# ZHSD-HDMI.net
KiCad netlist of a schematic drawn in Altium Designer
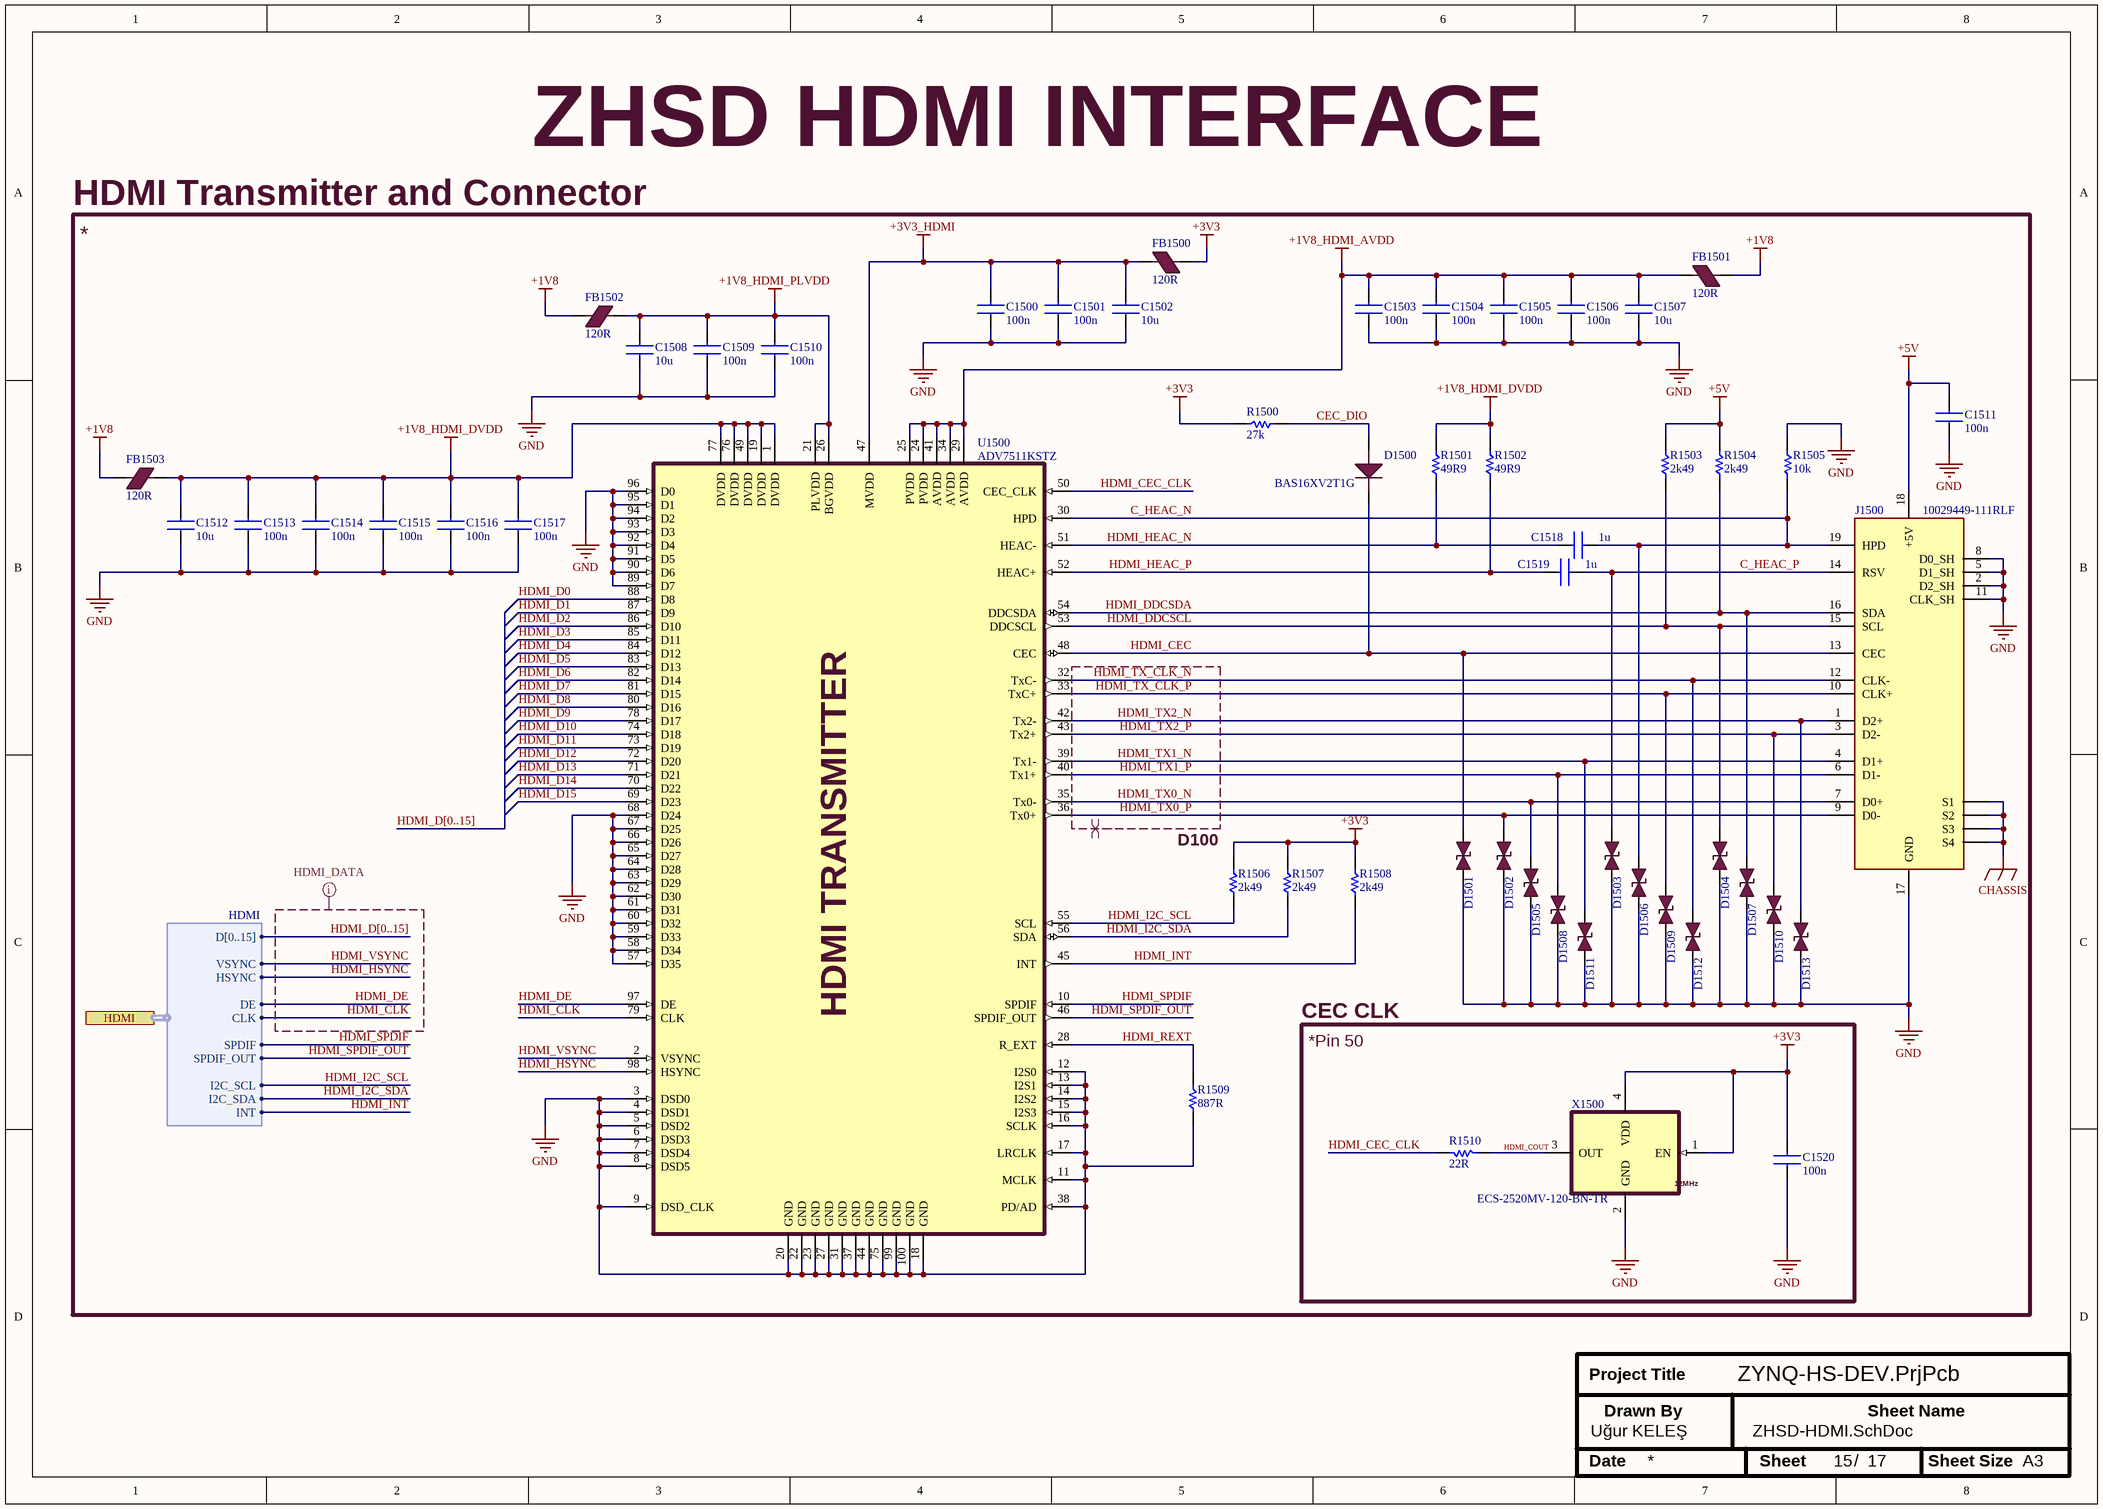
[diagram p0: ZHSD-HDMI.SchDoc]

(export (version "E")
  (design (tool "Eeschema 10.0.6"))
  (components
    (comp (ref "C1500")
      (value "100n")
      (footprint "0603CAPC1608X09N")
      (description "CAP CER 0.1UF 16V X7R 0402 (1005) ±10%")
      (fields (field (name "MANUFACTURER") "Murata Electronics") (field (name "MPN") "GRM155R71C104KA88J"))
      (libsource (lib "UK_Library") (part "GRM155R71C104KA88J"))
    )
    (comp (ref "C1501")
      (value "100n")
      (footprint "0603CAPC1608X09N")
      (description "CAP CER 0.1UF 16V X7R 0402 (1005) ±10%")
      (fields (field (name "MANUFACTURER") "Murata Electronics") (field (name "MPN") "GRM155R71C104KA88J"))
      (libsource (lib "UK_Library") (part "GRM155R71C104KA88J"))
    )
    (comp (ref "C1502")
      (value "10u")
      (footprint "0603CAPC1608X09N")
      (description "CAP CER 10UF 10V X7R 0603 (1608) ±20%")
      (fields (field (name "MANUFACTURER") "Murata Electronics") (field (name "MPN") "GRM188Z71A106MA73D"))
      (libsource (lib "UK_Library") (part "GRM188Z71A106MA73D"))
    )
    (comp (ref "C1503")
      (value "100n")
      (footprint "0603CAPC1608X09N")
      (description "CAP CER 0.1UF 16V X7R 0402 (1005) ±10%")
      (fields (field (name "MANUFACTURER") "Murata Electronics") (field (name "MPN") "GRM155R71C104KA88J"))
      (libsource (lib "UK_Library") (part "GRM155R71C104KA88J"))
    )
    (comp (ref "C1504")
      (value "100n")
      (footprint "0603CAPC1608X09N")
      (description "CAP CER 0.1UF 16V X7R 0402 (1005) ±10%")
      (fields (field (name "MANUFACTURER") "Murata Electronics") (field (name "MPN") "GRM155R71C104KA88J"))
      (libsource (lib "UK_Library") (part "GRM155R71C104KA88J"))
    )
    (comp (ref "C1505")
      (value "100n")
      (footprint "0603CAPC1608X09N")
      (description "CAP CER 0.1UF 16V X7R 0402 (1005) ±10%")
      (fields (field (name "MANUFACTURER") "Murata Electronics") (field (name "MPN") "GRM155R71C104KA88J"))
      (libsource (lib "UK_Library") (part "GRM155R71C104KA88J"))
    )
    (comp (ref "C1506")
      (value "100n")
      (footprint "0603CAPC1608X09N")
      (description "CAP CER 0.1UF 16V X7R 0402 (1005) ±10%")
      (fields (field (name "MANUFACTURER") "Murata Electronics") (field (name "MPN") "GRM155R71C104KA88J"))
      (libsource (lib "UK_Library") (part "GRM155R71C104KA88J"))
    )
    (comp (ref "C1507")
      (value "10u")
      (footprint "0603CAPC1608X09N")
      (description "CAP CER 10UF 10V X7R 0603 (1608) ±20%")
      (fields (field (name "MANUFACTURER") "Murata Electronics") (field (name "MPN") "GRM188Z71A106MA73D"))
      (libsource (lib "UK_Library") (part "GRM188Z71A106MA73D"))
    )
    (comp (ref "C1508")
      (value "10u")
      (footprint "0603CAPC1608X09N")
      (description "CAP CER 10UF 10V X7R 0603 (1608) ±20%")
      (fields (field (name "MANUFACTURER") "Murata Electronics") (field (name "MPN") "GRM188Z71A106MA73D"))
      (libsource (lib "UK_Library") (part "GRM188Z71A106MA73D"))
    )
    (comp (ref "C1509")
      (value "100n")
      (footprint "0603CAPC1608X09N")
      (description "CAP CER 0.1UF 16V X7R 0402 (1005) ±10%")
      (fields (field (name "MANUFACTURER") "Murata Electronics") (field (name "MPN") "GRM155R71C104KA88J"))
      (libsource (lib "UK_Library") (part "GRM155R71C104KA88J"))
    )
    (comp (ref "C1510")
      (value "100n")
      (footprint "0603CAPC1608X09N")
      (description "CAP CER 0.1UF 16V X7R 0402 (1005) ±10%")
      (fields (field (name "MANUFACTURER") "Murata Electronics") (field (name "MPN") "GRM155R71C104KA88J"))
      (libsource (lib "UK_Library") (part "GRM155R71C104KA88J"))
    )
    (comp (ref "C1511")
      (value "100n")
      (footprint "0603CAPC1608X09N")
      (description "CAP CER 0.1UF 16V X7R 0402 (1005) ±10%")
      (fields (field (name "MANUFACTURER") "Murata Electronics") (field (name "MPN") "GRM155R71C104KA88J"))
      (libsource (lib "UK_Library") (part "GRM155R71C104KA88J"))
    )
    (comp (ref "C1512")
      (value "10u")
      (footprint "0603CAPC1608X09N")
      (description "CAP CER 10UF 10V X7R 0603 (1608) ±20%")
      (fields (field (name "MANUFACTURER") "Murata Electronics") (field (name "MPN") "GRM188Z71A106MA73D"))
      (libsource (lib "UK_Library") (part "GRM188Z71A106MA73D"))
    )
    (comp (ref "C1513")
      (value "100n")
      (footprint "0603CAPC1608X09N")
      (description "CAP CER 0.1UF 16V X7R 0402 (1005) ±10%")
      (fields (field (name "MANUFACTURER") "Murata Electronics") (field (name "MPN") "GRM155R71C104KA88J"))
      (libsource (lib "UK_Library") (part "GRM155R71C104KA88J"))
    )
    (comp (ref "C1514")
      (value "100n")
      (footprint "0603CAPC1608X09N")
      (description "CAP CER 0.1UF 16V X7R 0402 (1005) ±10%")
      (fields (field (name "MANUFACTURER") "Murata Electronics") (field (name "MPN") "GRM155R71C104KA88J"))
      (libsource (lib "UK_Library") (part "GRM155R71C104KA88J"))
    )
    (comp (ref "C1515")
      (value "100n")
      (footprint "0603CAPC1608X09N")
      (description "CAP CER 0.1UF 16V X7R 0402 (1005) ±10%")
      (fields (field (name "MANUFACTURER") "Murata Electronics") (field (name "MPN") "GRM155R71C104KA88J"))
      (libsource (lib "UK_Library") (part "GRM155R71C104KA88J"))
    )
    (comp (ref "C1516")
      (value "100n")
      (footprint "0603CAPC1608X09N")
      (description "CAP CER 0.1UF 16V X7R 0402 (1005) ±10%")
      (fields (field (name "MANUFACTURER") "Murata Electronics") (field (name "MPN") "GRM155R71C104KA88J"))
      (libsource (lib "UK_Library") (part "GRM155R71C104KA88J"))
    )
    (comp (ref "C1517")
      (value "100n")
      (footprint "0603CAPC1608X09N")
      (description "CAP CER 0.1UF 16V X7R 0402 (1005) ±10%")
      (fields (field (name "MANUFACTURER") "Murata Electronics") (field (name "MPN") "GRM155R71C104KA88J"))
      (libsource (lib "UK_Library") (part "GRM155R71C104KA88J"))
    )
    (comp (ref "C1518")
      (value "1u")
      (footprint "0603CAPC1608X09N")
      (description "CAP CER 1UF 25V X5R 0603 (1608) ±10%")
      (fields
        (field (name "MANUFACTURER") "Murata Power Solutions Inc.")
        (field (name "MPN") "GRM188R61E105KA12D")
      )
      (libsource (lib "UK_Library") (part "GRM188R61E105KA12D"))
    )
    (comp (ref "C1519")
      (value "1u")
      (footprint "0603CAPC1608X09N")
      (description "CAP CER 1UF 25V X5R 0603 (1608) ±10%")
      (fields
        (field (name "MANUFACTURER") "Murata Power Solutions Inc.")
        (field (name "MPN") "GRM188R61E105KA12D")
      )
      (libsource (lib "UK_Library") (part "GRM188R61E105KA12D"))
    )
    (comp (ref "C1520")
      (value "100n")
      (footprint "0603CAPC1608X09N")
      (description "CAP CER 0.1UF 50V X7R 0603 (1608) ±10%")
      (fields (field (name "MANUFACTURER") "KEMET") (field (name "MPN") "C0603C104K5RACTU"))
      (libsource (lib "UK_Library") (part "C0603C104K5RACTU"))
    )
    (comp (ref "D1500")
      (value "BAS16XV2T1G")
      (footprint "SODFL160X50-2N")
      (description "DIODE STANDARD 100V 200MA SOD523")
      (fields (field (name "MANUFACTURER") "onsemi"))
      (libsource (lib "UK_Library") (part "BAS16XV2T1G"))
    )
    (comp (ref "D1501")
      (value "B72590D0050H160")
      (footprint "0402DIOC1005X06N")
      (description "Varistor 1 Circuit Surface Mount, MLCV 0402 (1005 Metric)")
      (fields (field (name "MANUFACTURER") "EPCOS - TDK Electronics"))
      (libsource (lib "UK_Library") (part "B72590D0050H160"))
    )
    (comp (ref "D1502")
      (value "B72590D0050H160")
      (footprint "0402DIOC1005X06N")
      (description "Varistor 1 Circuit Surface Mount, MLCV 0402 (1005 Metric)")
      (fields (field (name "MANUFACTURER") "EPCOS - TDK Electronics"))
      (libsource (lib "UK_Library") (part "B72590D0050H160"))
    )
    (comp (ref "D1503")
      (value "B72590D0050H160")
      (footprint "0402DIOC1005X06N")
      (description "Varistor 1 Circuit Surface Mount, MLCV 0402 (1005 Metric)")
      (fields (field (name "MANUFACTURER") "EPCOS - TDK Electronics"))
      (libsource (lib "UK_Library") (part "B72590D0050H160"))
    )
    (comp (ref "D1504")
      (value "B72590D0050H160")
      (footprint "0402DIOC1005X06N")
      (description "Varistor 1 Circuit Surface Mount, MLCV 0402 (1005 Metric)")
      (fields (field (name "MANUFACTURER") "EPCOS - TDK Electronics"))
      (libsource (lib "UK_Library") (part "B72590D0050H160"))
    )
    (comp (ref "D1505")
      (value "B72590D0050H160")
      (footprint "0402DIOC1005X06N")
      (description "Varistor 1 Circuit Surface Mount, MLCV 0402 (1005 Metric)")
      (fields (field (name "MANUFACTURER") "EPCOS - TDK Electronics"))
      (libsource (lib "UK_Library") (part "B72590D0050H160"))
    )
    (comp (ref "D1506")
      (value "B72590D0050H160")
      (footprint "0402DIOC1005X06N")
      (description "Varistor 1 Circuit Surface Mount, MLCV 0402 (1005 Metric)")
      (fields (field (name "MANUFACTURER") "EPCOS - TDK Electronics"))
      (libsource (lib "UK_Library") (part "B72590D0050H160"))
    )
    (comp (ref "D1507")
      (value "B72590D0050H160")
      (footprint "0402DIOC1005X06N")
      (description "Varistor 1 Circuit Surface Mount, MLCV 0402 (1005 Metric)")
      (fields (field (name "MANUFACTURER") "EPCOS - TDK Electronics"))
      (libsource (lib "UK_Library") (part "B72590D0050H160"))
    )
    (comp (ref "D1508")
      (value "B72590D0050H160")
      (footprint "0402DIOC1005X06N")
      (description "Varistor 1 Circuit Surface Mount, MLCV 0402 (1005 Metric)")
      (fields (field (name "MANUFACTURER") "EPCOS - TDK Electronics"))
      (libsource (lib "UK_Library") (part "B72590D0050H160"))
    )
    (comp (ref "D1509")
      (value "B72590D0050H160")
      (footprint "0402DIOC1005X06N")
      (description "Varistor 1 Circuit Surface Mount, MLCV 0402 (1005 Metric)")
      (fields (field (name "MANUFACTURER") "EPCOS - TDK Electronics"))
      (libsource (lib "UK_Library") (part "B72590D0050H160"))
    )
    (comp (ref "D1510")
      (value "B72590D0050H160")
      (footprint "0402DIOC1005X06N")
      (description "Varistor 1 Circuit Surface Mount, MLCV 0402 (1005 Metric)")
      (fields (field (name "MANUFACTURER") "EPCOS - TDK Electronics"))
      (libsource (lib "UK_Library") (part "B72590D0050H160"))
    )
    (comp (ref "D1511")
      (value "B72590D0050H160")
      (footprint "0402DIOC1005X06N")
      (description "Varistor 1 Circuit Surface Mount, MLCV 0402 (1005 Metric)")
      (fields (field (name "MANUFACTURER") "EPCOS - TDK Electronics"))
      (libsource (lib "UK_Library") (part "B72590D0050H160"))
    )
    (comp (ref "D1512")
      (value "B72590D0050H160")
      (footprint "0402DIOC1005X06N")
      (description "Varistor 1 Circuit Surface Mount, MLCV 0402 (1005 Metric)")
      (fields (field (name "MANUFACTURER") "EPCOS - TDK Electronics"))
      (libsource (lib "UK_Library") (part "B72590D0050H160"))
    )
    (comp (ref "D1513")
      (value "B72590D0050H160")
      (footprint "0402DIOC1005X06N")
      (description "Varistor 1 Circuit Surface Mount, MLCV 0402 (1005 Metric)")
      (fields (field (name "MANUFACTURER") "EPCOS - TDK Electronics"))
      (libsource (lib "UK_Library") (part "B72590D0050H160"))
    )
    (comp (ref "FB1500")
      (value "120R")
      (footprint "0603INDC1608X08N")
      (description "FERRITE BEAD 120 OHM 0603 (1608) 3A 25mOhm")
      (fields (field (name "MANUFACTURER") "Murata Electronics") (field (name "MPN") "BLM18SG121TN1D"))
      (libsource (lib "UK_Library") (part "BLM18SG121TN1D"))
    )
    (comp (ref "FB1501")
      (value "120R")
      (footprint "0603INDC1608X08N")
      (description "FERRITE BEAD 120 OHM 0603 (1608) 3A 25mOhm")
      (fields (field (name "MANUFACTURER") "Murata Electronics") (field (name "MPN") "BLM18SG121TN1D"))
      (libsource (lib "UK_Library") (part "BLM18SG121TN1D"))
    )
    (comp (ref "FB1502")
      (value "120R")
      (footprint "0603INDC1608X08N")
      (description "FERRITE BEAD 120 OHM 0603 (1608) 3A 25mOhm")
      (fields (field (name "MANUFACTURER") "Murata Electronics") (field (name "MPN") "BLM18SG121TN1D"))
      (libsource (lib "UK_Library") (part "BLM18SG121TN1D"))
    )
    (comp (ref "FB1503")
      (value "120R")
      (footprint "0603INDC1608X08N")
      (description "FERRITE BEAD 120 OHM 0603 (1608) 3A 25mOhm")
      (fields (field (name "MANUFACTURER") "Murata Electronics") (field (name "MPN") "BLM18SG121TN1D"))
      (libsource (lib "UK_Library") (part "BLM18SG121TN1D"))
    )
    (comp (ref "J1500")
      (value "10029449-111RLF")
      (footprint "AMPHENOL_10029449-111RLF")
      (description "CONN RCPT 1.4 HDMI 19POS SMD R/A")
      (fields (field (name "MANUFACTURER") "Amphenol ICC (FCI)"))
      (libsource (lib "UK_Library") (part "10029449-111RLF"))
    )
    (comp (ref "R1500")
      (value "27k")
      (footprint "0402RESC1005X04N")
      (description "RES 27K OHM 1% 1/16W 0402 (1005)")
      (fields (field (name "MANUFACTURER") "YAGEO") (field (name "MPN") "RC0402FR-0727KL"))
      (libsource (lib "UK_Library") (part "RC0402FR-0727KL"))
    )
    (comp (ref "R1501")
      (value "49R9")
      (footprint "0402RESC1005X04N")
      (description "RES 49.9 OHM 1% 1/16W 0402 (1005)")
      (fields (field (name "MANUFACTURER") "YAGEO") (field (name "MPN") "RC0402FR-0749R9L"))
      (libsource (lib "UK_Library") (part "RC0402FR-0749R9L"))
    )
    (comp (ref "R1502")
      (value "49R9")
      (footprint "0402RESC1005X04N")
      (description "RES 49.9 OHM 1% 1/16W 0402 (1005)")
      (fields (field (name "MANUFACTURER") "YAGEO") (field (name "MPN") "RC0402FR-0749R9L"))
      (libsource (lib "UK_Library") (part "RC0402FR-0749R9L"))
    )
    (comp (ref "R1503")
      (value "2k49")
      (footprint "0402RESC1005X04N")
      (description "RES 2.49K OHM 1% 1/16W 0402 (1005)")
      (fields (field (name "MANUFACTURER") "YAGEO") (field (name "MPN") "RC0402FR-132K49L"))
      (libsource (lib "UK_Library") (part "RC0402FR-132K49L"))
    )
    (comp (ref "R1504")
      (value "2k49")
      (footprint "0402RESC1005X04N")
      (description "RES 2.49K OHM 1% 1/16W 0402 (1005)")
      (fields (field (name "MANUFACTURER") "YAGEO") (field (name "MPN") "RC0402FR-132K49L"))
      (libsource (lib "UK_Library") (part "RC0402FR-132K49L"))
    )
    (comp (ref "R1505")
      (value "10k")
      (footprint "0603RESC1608X05N")
      (description "RES 10K OHM 1% 1/10W 0603(1608)")
      (fields (field (name "MANUFACTURER") "YAGEO") (field (name "MPN") "RC0603FR-0710KL"))
      (libsource (lib "UK_Library") (part "RC0603FR-0710KL"))
    )
    (comp (ref "R1506")
      (value "2k49")
      (footprint "0402RESC1005X04N")
      (description "RES 2.49K OHM 1% 1/16W 0402 (1005)")
      (fields (field (name "MANUFACTURER") "YAGEO") (field (name "MPN") "RC0402FR-132K49L"))
      (libsource (lib "UK_Library") (part "RC0402FR-132K49L"))
    )
    (comp (ref "R1507")
      (value "2k49")
      (footprint "0402RESC1005X04N")
      (description "RES 2.49K OHM 1% 1/16W 0402 (1005)")
      (fields (field (name "MANUFACTURER") "YAGEO") (field (name "MPN") "RC0402FR-132K49L"))
      (libsource (lib "UK_Library") (part "RC0402FR-132K49L"))
    )
    (comp (ref "R1508")
      (value "2k49")
      (footprint "0402RESC1005X04N")
      (description "RES 2.49K OHM 1% 1/16W 0402 (1005)")
      (fields (field (name "MANUFACTURER") "YAGEO") (field (name "MPN") "RC0402FR-132K49L"))
      (libsource (lib "UK_Library") (part "RC0402FR-132K49L"))
    )
    (comp (ref "R1509")
      (value "887R")
      (footprint "0603RESC1608X05N")
      (description "RES 887 OHM 1% 1/10W 0603 (1608)")
      (fields (field (name "MANUFACTURER") "YAGEO") (field (name "MPN") "RC0603FR-07887RL"))
      (libsource (lib "UK_Library") (part "RC0603FR-07887RL"))
    )
    (comp (ref "R1510")
      (value "22R")
      (footprint "0603RESC1608X05N")
      (description "RES 22 OHM 1% 1/10W 0603 (1608)")
      (fields (field (name "MANUFACTURER") "YAGEO") (field (name "MPN") "RC0603FR-0722RL"))
      (libsource (lib "UK_Library") (part "RC0603FR-0722RL"))
    )
    (comp (ref "U1500")
      (value "ADV7511KSTZ")
      (footprint "LQFP50P1600X1600X160-100N")
      (description "225 MHz, High Performance HDMI® Transmitter with ARC")
      (fields (field (name "MANUFACTURER") "Analog Devices Inc./Maxim Integrated"))
      (libsource (lib "UK_Library") (part "ADV7511KSTZ"))
    )
    (comp (ref "X1500")
      (value "ECS-2520MV-120-BN-TR")
      (footprint "XTAL_2520")
      (description "XTAL OSC XO 12.0000MHZ CMOS SMD")
      (fields (field (name "MANUFACTURER") "ECS Inc."))
      (libsource (lib "UK_Library") (part "ECS-2520MV-120-BN-TR"))
    )
  )
  (nets
    (net (code "2") (name "+1V8") (class "Default")
      (node (ref "FB1501") (pin "1") (pinfunction "1_1") (pintype "passive"))
      (node (ref "FB1502") (pin "1") (pinfunction "1_1") (pintype "passive"))
      (node (ref "FB1503") (pin "1") (pinfunction "1_1") (pintype "passive"))
    )
    (net (code "3") (name "+1V8_HDMI_AVDD") (class "Default")
      (node (ref "C1503") (pin "2") (pinfunction "2_2") (pintype "passive"))
      (node (ref "C1504") (pin "2") (pinfunction "2_2") (pintype "passive"))
      (node (ref "C1505") (pin "2") (pinfunction "2_2") (pintype "passive"))
      (node (ref "C1506") (pin "2") (pinfunction "2_2") (pintype "passive"))
      (node (ref "C1507") (pin "2") (pinfunction "2_2") (pintype "passive"))
      (node (ref "FB1501") (pin "2") (pinfunction "2_2") (pintype "passive"))
      (node (ref "U1500") (pin "24") (pinfunction "PVDD_24") (pintype "power_in"))
      (node (ref "U1500") (pin "25") (pinfunction "PVDD_25") (pintype "power_in"))
      (node (ref "U1500") (pin "29") (pinfunction "AVDD_29") (pintype "power_in"))
      (node (ref "U1500") (pin "34") (pinfunction "AVDD_34") (pintype "power_in"))
      (node (ref "U1500") (pin "41") (pinfunction "AVDD_41") (pintype "power_in"))
    )
    (net (code "4") (name "+1V8_HDMI_DVDD") (class "Default")
      (node (ref "C1512") (pin "2") (pinfunction "2_2") (pintype "passive"))
      (node (ref "C1513") (pin "2") (pinfunction "2_2") (pintype "passive"))
      (node (ref "C1514") (pin "2") (pinfunction "2_2") (pintype "passive"))
      (node (ref "C1515") (pin "2") (pinfunction "2_2") (pintype "passive"))
      (node (ref "C1516") (pin "2") (pinfunction "2_2") (pintype "passive"))
      (node (ref "C1517") (pin "2") (pinfunction "2_2") (pintype "passive"))
      (node (ref "FB1503") (pin "2") (pinfunction "2_2") (pintype "passive"))
      (node (ref "R1501") (pin "2") (pinfunction "2_2") (pintype "passive"))
      (node (ref "R1502") (pin "2") (pinfunction "2_2") (pintype "passive"))
      (node (ref "U1500") (pin "1") (pinfunction "DVDD_1") (pintype "power_in"))
      (node (ref "U1500") (pin "19") (pinfunction "DVDD_19") (pintype "power_in"))
      (node (ref "U1500") (pin "49") (pinfunction "DVDD_49") (pintype "power_in"))
      (node (ref "U1500") (pin "76") (pinfunction "DVDD_76") (pintype "power_in"))
      (node (ref "U1500") (pin "77") (pinfunction "DVDD_77") (pintype "power_in"))
    )
    (net (code "5") (name "+1V8_HDMI_PLVDD") (class "Default")
      (node (ref "C1508") (pin "2") (pinfunction "2_2") (pintype "passive"))
      (node (ref "C1509") (pin "2") (pinfunction "2_2") (pintype "passive"))
      (node (ref "C1510") (pin "2") (pinfunction "2_2") (pintype "passive"))
      (node (ref "FB1502") (pin "2") (pinfunction "2_2") (pintype "passive"))
      (node (ref "U1500") (pin "21") (pinfunction "PLVDD_21") (pintype "power_in"))
      (node (ref "U1500") (pin "26") (pinfunction "BGVDD_26") (pintype "power_in"))
    )
    (net (code "6") (name "+3V3") (class "Default")
      (node (ref "C1520") (pin "2") (pinfunction "2_2") (pintype "passive"))
      (node (ref "FB1500") (pin "1") (pinfunction "1_1") (pintype "passive"))
      (node (ref "R1500") (pin "2") (pinfunction "2_2") (pintype "passive"))
      (node (ref "R1506") (pin "2") (pinfunction "2_2") (pintype "passive"))
      (node (ref "R1507") (pin "2") (pinfunction "2_2") (pintype "passive"))
      (node (ref "R1508") (pin "2") (pinfunction "2_2") (pintype "passive"))
      (node (ref "X1500") (pin "1") (pinfunction "EN_1") (pintype "input"))
      (node (ref "X1500") (pin "4") (pinfunction "VDD_4") (pintype "power_in"))
    )
    (net (code "7") (name "+3V3_HDMI") (class "Default")
      (node (ref "C1500") (pin "2") (pinfunction "2_2") (pintype "passive"))
      (node (ref "C1501") (pin "2") (pinfunction "2_2") (pintype "passive"))
      (node (ref "C1502") (pin "2") (pinfunction "2_2") (pintype "passive"))
      (node (ref "FB1500") (pin "2") (pinfunction "2_2") (pintype "passive"))
      (node (ref "U1500") (pin "47") (pinfunction "MVDD_47") (pintype "power_in"))
    )
    (net (code "8") (name "+5V") (class "Default")
      (node (ref "C1511") (pin "2") (pinfunction "2_2") (pintype "passive"))
      (node (ref "J1500") (pin "18") (pinfunction "+5V_18") (pintype "passive"))
      (node (ref "R1503") (pin "2") (pinfunction "2_2") (pintype "passive"))
      (node (ref "R1504") (pin "2") (pinfunction "2_2") (pintype "passive"))
    )
    (net (code "9") (name "/CEC_DIO") (class "Default")
      (node (ref "D1500") (pin "A") (pinfunction "2_A") (pintype "passive"))
      (node (ref "R1500") (pin "1") (pinfunction "1_1") (pintype "passive"))
    )
    (net (code "10") (name "/C_HEAC_N") (class "Default")
      (node (ref "C1518") (pin "2") (pinfunction "2_2") (pintype "passive"))
      (node (ref "D1506") (pin "2") (pinfunction "2_2") (pintype "passive"))
      (node (ref "J1500") (pin "19") (pinfunction "HPD_19") (pintype "passive"))
      (node (ref "R1505") (pin "2") (pinfunction "2_2") (pintype "passive"))
      (node (ref "U1500") (pin "30") (pinfunction "HPD_30") (pintype "input"))
    )
    (net (code "11") (name "/C_HEAC_P") (class "Default")
      (node (ref "C1519") (pin "2") (pinfunction "2_2") (pintype "passive"))
      (node (ref "D1503") (pin "2") (pinfunction "2_2") (pintype "passive"))
      (node (ref "J1500") (pin "14") (pinfunction "RSV_14") (pintype "passive"))
    )
    (net (code "12") (name "/HDMI_CEC") (class "Default")
      (node (ref "D1500") (pin "C") (pinfunction "1_C") (pintype "passive"))
      (node (ref "D1501") (pin "2") (pinfunction "2_2") (pintype "passive"))
      (node (ref "J1500") (pin "13") (pinfunction "CEC_13") (pintype "passive"))
      (node (ref "U1500") (pin "48") (pinfunction "CEC_48") (pintype "bidirectional"))
    )
    (net (code "13") (name "/HDMI_CEC_CLK") (class "Default")
      (node (ref "R1510") (pin "1") (pinfunction "1_1") (pintype "passive"))
      (node (ref "U1500") (pin "50") (pinfunction "CEC_CLK_50") (pintype "input"))
    )
    (net (code "14") (name "/HDMI_CLK") (class "Default")
      (node (ref "U1500") (pin "79") (pinfunction "CLK_79") (pintype "input"))
    )
    (net (code "15") (name "/HDMI_COUT") (class "Default")
      (node (ref "R1510") (pin "2") (pinfunction "2_2") (pintype "passive"))
      (node (ref "X1500") (pin "3") (pinfunction "OUT_3") (pintype "passive"))
    )
    (net (code "16") (name "/HDMI_D0") (class "Default")
      (node (ref "U1500") (pin "88") (pinfunction "D8_88") (pintype "input"))
    )
    (net (code "17") (name "/HDMI_D1") (class "Default")
      (node (ref "U1500") (pin "87") (pinfunction "D9_87") (pintype "input"))
    )
    (net (code "18") (name "/HDMI_D2") (class "Default")
      (node (ref "U1500") (pin "86") (pinfunction "D10_86") (pintype "input"))
    )
    (net (code "19") (name "/HDMI_D3") (class "Default")
      (node (ref "U1500") (pin "85") (pinfunction "D11_85") (pintype "input"))
    )
    (net (code "20") (name "/HDMI_D4") (class "Default")
      (node (ref "U1500") (pin "84") (pinfunction "D12_84") (pintype "input"))
    )
    (net (code "21") (name "/HDMI_D5") (class "Default")
      (node (ref "U1500") (pin "83") (pinfunction "D13_83") (pintype "input"))
    )
    (net (code "22") (name "/HDMI_D6") (class "Default")
      (node (ref "U1500") (pin "82") (pinfunction "D14_82") (pintype "input"))
    )
    (net (code "23") (name "/HDMI_D7") (class "Default")
      (node (ref "U1500") (pin "81") (pinfunction "D15_81") (pintype "input"))
    )
    (net (code "24") (name "/HDMI_D8") (class "Default")
      (node (ref "U1500") (pin "80") (pinfunction "D16_80") (pintype "input"))
    )
    (net (code "25") (name "/HDMI_D9") (class "Default")
      (node (ref "U1500") (pin "78") (pinfunction "D17_78") (pintype "input"))
    )
    (net (code "26") (name "/HDMI_D10") (class "Default")
      (node (ref "U1500") (pin "74") (pinfunction "D18_74") (pintype "input"))
    )
    (net (code "27") (name "/HDMI_D11") (class "Default")
      (node (ref "U1500") (pin "73") (pinfunction "D19_73") (pintype "input"))
    )
    (net (code "28") (name "/HDMI_D12") (class "Default")
      (node (ref "U1500") (pin "72") (pinfunction "D20_72") (pintype "input"))
    )
    (net (code "29") (name "/HDMI_D13") (class "Default")
      (node (ref "U1500") (pin "71") (pinfunction "D21_71") (pintype "input"))
    )
    (net (code "30") (name "/HDMI_D14") (class "Default")
      (node (ref "U1500") (pin "70") (pinfunction "D22_70") (pintype "input"))
    )
    (net (code "31") (name "/HDMI_D15") (class "Default")
      (node (ref "U1500") (pin "69") (pinfunction "D23_69") (pintype "input"))
    )
    (net (code "32") (name "/HDMI_DDCSCL") (class "Default")
      (node (ref "D1504") (pin "2") (pinfunction "2_2") (pintype "passive"))
      (node (ref "J1500") (pin "15") (pinfunction "SCL_15") (pintype "passive"))
      (node (ref "R1503") (pin "1") (pinfunction "1_1") (pintype "passive"))
      (node (ref "U1500") (pin "53") (pinfunction "DDCSCL_53") (pintype "output"))
    )
    (net (code "33") (name "/HDMI_DDCSDA") (class "Default")
      (node (ref "D1507") (pin "2") (pinfunction "2_2") (pintype "passive"))
      (node (ref "J1500") (pin "16") (pinfunction "SDA_16") (pintype "passive"))
      (node (ref "R1504") (pin "1") (pinfunction "1_1") (pintype "passive"))
      (node (ref "U1500") (pin "54") (pinfunction "DDCSDA_54") (pintype "bidirectional"))
    )
    (net (code "34") (name "/HDMI_DE") (class "Default")
      (node (ref "U1500") (pin "97") (pinfunction "DE_97") (pintype "input"))
    )
    (net (code "36") (name "/HDMI_HEAC_N") (class "Default")
      (node (ref "C1518") (pin "1") (pinfunction "1_1") (pintype "passive"))
      (node (ref "R1501") (pin "1") (pinfunction "1_1") (pintype "passive"))
      (node (ref "U1500") (pin "51") (pinfunction "HEAC-_51") (pintype "input"))
    )
    (net (code "37") (name "/HDMI_HEAC_P") (class "Default")
      (node (ref "C1519") (pin "1") (pinfunction "1_1") (pintype "passive"))
      (node (ref "R1502") (pin "1") (pinfunction "1_1") (pintype "passive"))
      (node (ref "U1500") (pin "52") (pinfunction "HEAC+_52") (pintype "input"))
    )
    (net (code "38") (name "/HDMI_HSYNC") (class "Default")
      (node (ref "U1500") (pin "98") (pinfunction "HSYNC_98") (pintype "input"))
    )
    (net (code "39") (name "/HDMI_I2C_SCL") (class "Default")
      (node (ref "R1506") (pin "1") (pinfunction "1_1") (pintype "passive"))
      (node (ref "U1500") (pin "55") (pinfunction "SCL_55") (pintype "input"))
    )
    (net (code "40") (name "/HDMI_I2C_SDA") (class "Default")
      (node (ref "R1507") (pin "1") (pinfunction "1_1") (pintype "passive"))
      (node (ref "U1500") (pin "56") (pinfunction "SDA_56") (pintype "bidirectional"))
    )
    (net (code "41") (name "/HDMI_INT") (class "Default")
      (node (ref "R1508") (pin "1") (pinfunction "1_1") (pintype "passive"))
      (node (ref "U1500") (pin "45") (pinfunction "INT_45") (pintype "output"))
    )
    (net (code "42") (name "/HDMI_REXT") (class "Default")
      (node (ref "R1509") (pin "2") (pinfunction "2_2") (pintype "passive"))
      (node (ref "U1500") (pin "28") (pinfunction "R_EXT_28") (pintype "input"))
    )
    (net (code "43") (name "/HDMI_SPDIF") (class "Default")
      (node (ref "U1500") (pin "10") (pinfunction "SPDIF_10") (pintype "input"))
    )
    (net (code "44") (name "/HDMI_SPDIF_OUT") (class "Default")
      (node (ref "U1500") (pin "46") (pinfunction "SPDIF_OUT_46") (pintype "output"))
    )
    (net (code "45") (name "/HDMI_TX0_N") (class "Default")
      (node (ref "D1505") (pin "2") (pinfunction "2_2") (pintype "passive"))
      (node (ref "J1500") (pin "7") (pinfunction "D0+_7") (pintype "passive"))
      (node (ref "U1500") (pin "35") (pinfunction "Tx0-_35") (pintype "output"))
    )
    (net (code "46") (name "/HDMI_TX0_P") (class "Default")
      (node (ref "D1502") (pin "2") (pinfunction "2_2") (pintype "passive"))
      (node (ref "J1500") (pin "9") (pinfunction "D0-_9") (pintype "passive"))
      (node (ref "U1500") (pin "36") (pinfunction "Tx0+_36") (pintype "output"))
    )
    (net (code "47") (name "/HDMI_TX1_N") (class "Default")
      (node (ref "D1511") (pin "2") (pinfunction "2_2") (pintype "passive"))
      (node (ref "J1500") (pin "4") (pinfunction "D1+_4") (pintype "passive"))
      (node (ref "U1500") (pin "39") (pinfunction "Tx1-_39") (pintype "output"))
    )
    (net (code "48") (name "/HDMI_TX1_P") (class "Default")
      (node (ref "D1508") (pin "2") (pinfunction "2_2") (pintype "passive"))
      (node (ref "J1500") (pin "6") (pinfunction "D1-_6") (pintype "passive"))
      (node (ref "U1500") (pin "40") (pinfunction "Tx1+_40") (pintype "output"))
    )
    (net (code "49") (name "/HDMI_TX2_N") (class "Default")
      (node (ref "D1513") (pin "2") (pinfunction "2_2") (pintype "passive"))
      (node (ref "J1500") (pin "1") (pinfunction "D2+_1") (pintype "passive"))
      (node (ref "U1500") (pin "42") (pinfunction "Tx2-_42") (pintype "output"))
    )
    (net (code "50") (name "/HDMI_TX2_P") (class "Default")
      (node (ref "D1510") (pin "2") (pinfunction "2_2") (pintype "passive"))
      (node (ref "J1500") (pin "3") (pinfunction "D2-_3") (pintype "passive"))
      (node (ref "U1500") (pin "43") (pinfunction "Tx2+_43") (pintype "output"))
    )
    (net (code "51") (name "/HDMI_TX_CLK_N") (class "Default")
      (node (ref "D1512") (pin "2") (pinfunction "2_2") (pintype "passive"))
      (node (ref "J1500") (pin "12") (pinfunction "CLK-_12") (pintype "passive"))
      (node (ref "U1500") (pin "32") (pinfunction "TxC-_32") (pintype "output"))
    )
    (net (code "52") (name "/HDMI_TX_CLK_P") (class "Default")
      (node (ref "D1509") (pin "2") (pinfunction "2_2") (pintype "passive"))
      (node (ref "J1500") (pin "10") (pinfunction "CLK+_10") (pintype "passive"))
      (node (ref "U1500") (pin "33") (pinfunction "TxC+_33") (pintype "output"))
    )
    (net (code "53") (name "/HDMI_VSYNC") (class "Default")
      (node (ref "U1500") (pin "2") (pinfunction "VSYNC_2") (pintype "input"))
    )
    (net (code "55") (name "CHASSIS") (class "Default")
      (node (ref "J1500") (pin "S1") (pinfunction "S1_S1") (pintype "passive"))
      (node (ref "J1500") (pin "S2") (pinfunction "S2_S2") (pintype "passive"))
      (node (ref "J1500") (pin "S3") (pinfunction "S3_S3") (pintype "passive"))
      (node (ref "J1500") (pin "S4") (pinfunction "S4_S4") (pintype "passive"))
    )
    (net (code "56") (name "GND") (class "Default")
      (node (ref "C1500") (pin "1") (pinfunction "1_1") (pintype "passive"))
      (node (ref "C1501") (pin "1") (pinfunction "1_1") (pintype "passive"))
      (node (ref "C1502") (pin "1") (pinfunction "1_1") (pintype "passive"))
      (node (ref "C1503") (pin "1") (pinfunction "1_1") (pintype "passive"))
      (node (ref "C1504") (pin "1") (pinfunction "1_1") (pintype "passive"))
      (node (ref "C1505") (pin "1") (pinfunction "1_1") (pintype "passive"))
      (node (ref "C1506") (pin "1") (pinfunction "1_1") (pintype "passive"))
      (node (ref "C1507") (pin "1") (pinfunction "1_1") (pintype "passive"))
      (node (ref "C1508") (pin "1") (pinfunction "1_1") (pintype "passive"))
      (node (ref "C1509") (pin "1") (pinfunction "1_1") (pintype "passive"))
      (node (ref "C1510") (pin "1") (pinfunction "1_1") (pintype "passive"))
      (node (ref "C1511") (pin "1") (pinfunction "1_1") (pintype "passive"))
      (node (ref "C1512") (pin "1") (pinfunction "1_1") (pintype "passive"))
      (node (ref "C1513") (pin "1") (pinfunction "1_1") (pintype "passive"))
      (node (ref "C1514") (pin "1") (pinfunction "1_1") (pintype "passive"))
      (node (ref "C1515") (pin "1") (pinfunction "1_1") (pintype "passive"))
      (node (ref "C1516") (pin "1") (pinfunction "1_1") (pintype "passive"))
      (node (ref "C1517") (pin "1") (pinfunction "1_1") (pintype "passive"))
      (node (ref "C1520") (pin "1") (pinfunction "1_1") (pintype "passive"))
      (node (ref "D1501") (pin "1") (pinfunction "1_1") (pintype "passive"))
      (node (ref "D1502") (pin "1") (pinfunction "1_1") (pintype "passive"))
      (node (ref "D1503") (pin "1") (pinfunction "1_1") (pintype "passive"))
      (node (ref "D1504") (pin "1") (pinfunction "1_1") (pintype "passive"))
      (node (ref "D1505") (pin "1") (pinfunction "1_1") (pintype "passive"))
      (node (ref "D1506") (pin "1") (pinfunction "1_1") (pintype "passive"))
      (node (ref "D1507") (pin "1") (pinfunction "1_1") (pintype "passive"))
      (node (ref "D1508") (pin "1") (pinfunction "1_1") (pintype "passive"))
      (node (ref "D1509") (pin "1") (pinfunction "1_1") (pintype "passive"))
      (node (ref "D1510") (pin "1") (pinfunction "1_1") (pintype "passive"))
      (node (ref "D1511") (pin "1") (pinfunction "1_1") (pintype "passive"))
      (node (ref "D1512") (pin "1") (pinfunction "1_1") (pintype "passive"))
      (node (ref "D1513") (pin "1") (pinfunction "1_1") (pintype "passive"))
      (node (ref "J1500") (pin "11") (pinfunction "CLK_SH_11") (pintype "passive"))
      (node (ref "J1500") (pin "17") (pinfunction "GND_17") (pintype "passive"))
      (node (ref "J1500") (pin "2") (pinfunction "D2_SH_2") (pintype "passive"))
      (node (ref "J1500") (pin "5") (pinfunction "D1_SH_5") (pintype "passive"))
      (node (ref "J1500") (pin "8") (pinfunction "D0_SH_8") (pintype "passive"))
      (node (ref "R1505") (pin "1") (pinfunction "1_1") (pintype "passive"))
      (node (ref "R1509") (pin "1") (pinfunction "1_1") (pintype "passive"))
      (node (ref "U1500") (pin "100") (pinfunction "GND_100") (pintype "power_in"))
      (node (ref "U1500") (pin "11") (pinfunction "MCLK_11") (pintype "input"))
      (node (ref "U1500") (pin "12") (pinfunction "I2S0_12") (pintype "input"))
      (node (ref "U1500") (pin "13") (pinfunction "I2S1_13") (pintype "input"))
      (node (ref "U1500") (pin "14") (pinfunction "I2S2_14") (pintype "input"))
      (node (ref "U1500") (pin "15") (pinfunction "I2S3_15") (pintype "input"))
      (node (ref "U1500") (pin "16") (pinfunction "SCLK_16") (pintype "input"))
      (node (ref "U1500") (pin "17") (pinfunction "LRCLK_17") (pintype "input"))
      (node (ref "U1500") (pin "18") (pinfunction "GND_18") (pintype "power_in"))
      (node (ref "U1500") (pin "20") (pinfunction "GND_20") (pintype "power_in"))
      (node (ref "U1500") (pin "22") (pinfunction "GND_22") (pintype "power_in"))
      (node (ref "U1500") (pin "23") (pinfunction "GND_23") (pintype "power_in"))
      (node (ref "U1500") (pin "27") (pinfunction "GND_27") (pintype "power_in"))
      (node (ref "U1500") (pin "3") (pinfunction "DSD0_3") (pintype "input"))
      (node (ref "U1500") (pin "31") (pinfunction "GND_31") (pintype "power_in"))
      (node (ref "U1500") (pin "37") (pinfunction "GND_37") (pintype "power_in"))
      (node (ref "U1500") (pin "38") (pinfunction "PD/AD_38") (pintype "input"))
      (node (ref "U1500") (pin "4") (pinfunction "DSD1_4") (pintype "input"))
      (node (ref "U1500") (pin "44") (pinfunction "GND_44") (pintype "power_in"))
      (node (ref "U1500") (pin "5") (pinfunction "DSD2_5") (pintype "input"))
      (node (ref "U1500") (pin "57") (pinfunction "D35_57") (pintype "input"))
      (node (ref "U1500") (pin "58") (pinfunction "D34_58") (pintype "input"))
      (node (ref "U1500") (pin "59") (pinfunction "D33_59") (pintype "input"))
      (node (ref "U1500") (pin "6") (pinfunction "DSD3_6") (pintype "input"))
      (node (ref "U1500") (pin "60") (pinfunction "D32_60") (pintype "input"))
      (node (ref "U1500") (pin "61") (pinfunction "D31_61") (pintype "input"))
      (node (ref "U1500") (pin "62") (pinfunction "D30_62") (pintype "input"))
      (node (ref "U1500") (pin "63") (pinfunction "D29_63") (pintype "input"))
      (node (ref "U1500") (pin "64") (pinfunction "D28_64") (pintype "input"))
      (node (ref "U1500") (pin "65") (pinfunction "D27_65") (pintype "input"))
      (node (ref "U1500") (pin "66") (pinfunction "D26_66") (pintype "input"))
      (node (ref "U1500") (pin "67") (pinfunction "D25_67") (pintype "input"))
      (node (ref "U1500") (pin "68") (pinfunction "D24_68") (pintype "input"))
      (node (ref "U1500") (pin "7") (pinfunction "DSD4_7") (pintype "input"))
      (node (ref "U1500") (pin "75") (pinfunction "GND_75") (pintype "power_in"))
      (node (ref "U1500") (pin "8") (pinfunction "DSD5_8") (pintype "input"))
      (node (ref "U1500") (pin "89") (pinfunction "D7_89") (pintype "input"))
      (node (ref "U1500") (pin "9") (pinfunction "DSD_CLK_9") (pintype "input"))
      (node (ref "U1500") (pin "90") (pinfunction "D6_90") (pintype "input"))
      (node (ref "U1500") (pin "91") (pinfunction "D5_91") (pintype "input"))
      (node (ref "U1500") (pin "92") (pinfunction "D4_92") (pintype "input"))
      (node (ref "U1500") (pin "93") (pinfunction "D3_93") (pintype "input"))
      (node (ref "U1500") (pin "94") (pinfunction "D2_94") (pintype "input"))
      (node (ref "U1500") (pin "95") (pinfunction "D1_95") (pintype "input"))
      (node (ref "U1500") (pin "96") (pinfunction "D0_96") (pintype "input"))
      (node (ref "U1500") (pin "99") (pinfunction "GND_99") (pintype "power_in"))
      (node (ref "X1500") (pin "2") (pinfunction "GND_2") (pintype "power_in"))
    )
  )
)
